# TriggerBoardv2.net
KiCad netlist of a schematic drawn in EAGLE
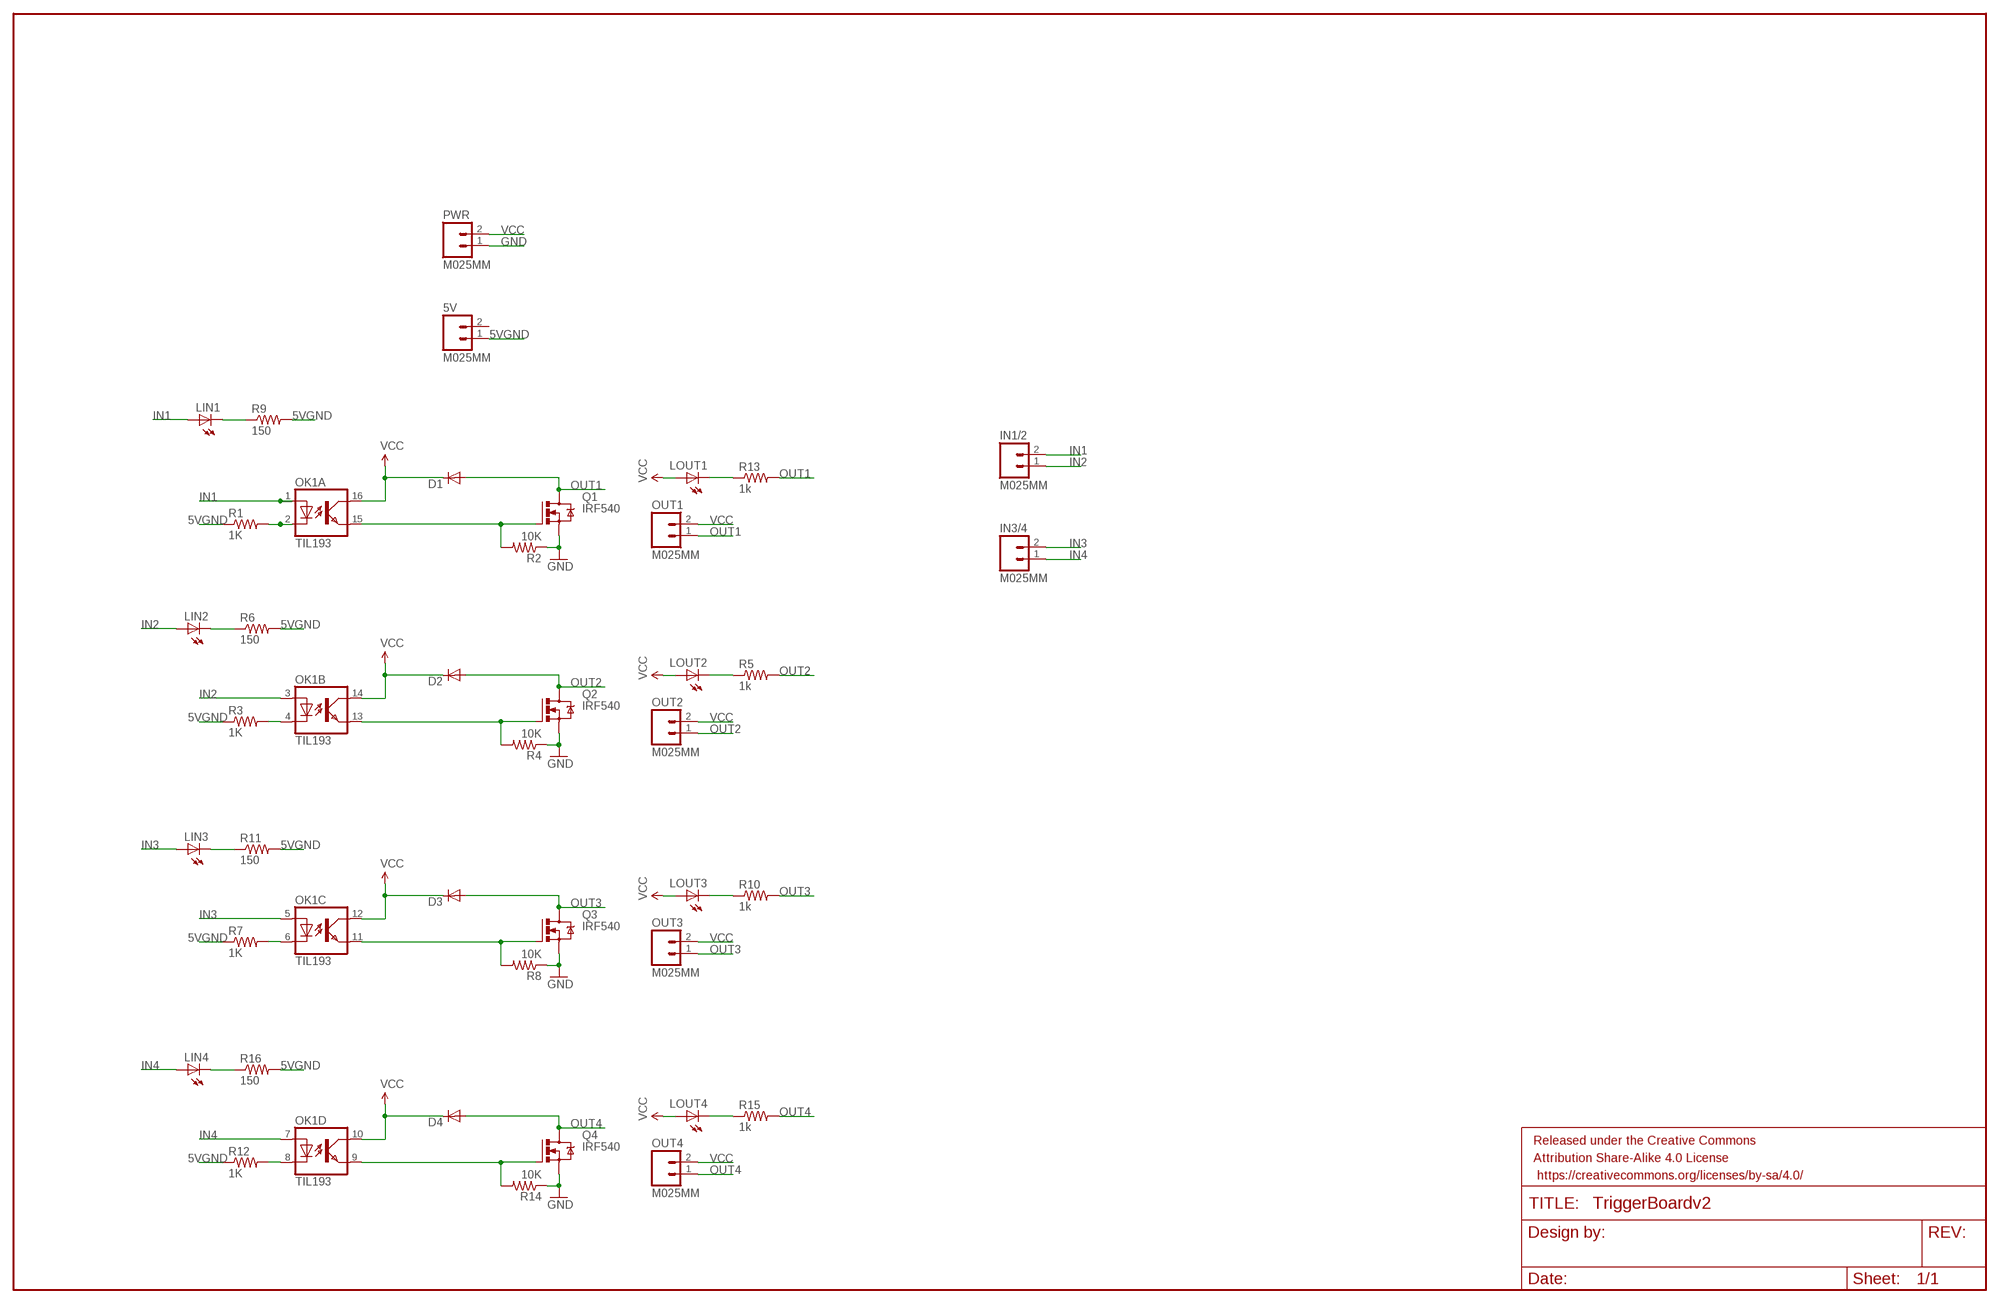
[diagram p0: schematic, sheet 1]

(export (version "E")
  (design (tool "Eeschema 10.0.6"))
  (components
    (comp (ref "5V")
      (value "M025MM")
      (footprint "eagle-import:SCREWTERMINAL-5MM-2")
      (libsource (lib "eagle-import") (part "M025MM"))
    )
    (comp (ref "D1")
      (value "DIODEPTH")
      (footprint "eagle-import:DIODE-1N4001")
      (libsource (lib "eagle-import") (part "DIODEPTH"))
    )
    (comp (ref "D2")
      (value "DIODEPTH")
      (footprint "eagle-import:DIODE-1N4001")
      (libsource (lib "eagle-import") (part "DIODEPTH"))
    )
    (comp (ref "D3")
      (value "DIODEPTH")
      (footprint "eagle-import:DIODE-1N4001")
      (libsource (lib "eagle-import") (part "DIODEPTH"))
    )
    (comp (ref "D4")
      (value "DIODEPTH")
      (footprint "eagle-import:DIODE-1N4001")
      (libsource (lib "eagle-import") (part "DIODEPTH"))
    )
    (comp (ref "FRAME1")
      (value "FRAME-LEDGER")
      (footprint "eagle-import:CREATIVE_COMMONS")
      (libsource (lib "eagle-import") (part "FRAME-LEDGER"))
    )
    (comp (ref "IN1/2")
      (value "M025MM")
      (footprint "eagle-import:SCREWTERMINAL-5MM-2")
      (libsource (lib "eagle-import") (part "M025MM"))
    )
    (comp (ref "IN3/4")
      (value "M025MM")
      (footprint "eagle-import:SCREWTERMINAL-5MM-2")
      (libsource (lib "eagle-import") (part "M025MM"))
    )
    (comp (ref "LIN1")
      (value "LED3MM")
      (footprint "eagle-import:LED3MM")
      (libsource (lib "eagle-import") (part "LED3MM"))
    )
    (comp (ref "LIN2")
      (value "LED3MM")
      (footprint "eagle-import:LED3MM")
      (libsource (lib "eagle-import") (part "LED3MM"))
    )
    (comp (ref "LIN3")
      (value "LED3MM")
      (footprint "eagle-import:LED3MM")
      (libsource (lib "eagle-import") (part "LED3MM"))
    )
    (comp (ref "LIN4")
      (value "LED3MM")
      (footprint "eagle-import:LED3MM")
      (libsource (lib "eagle-import") (part "LED3MM"))
    )
    (comp (ref "LOUT1")
      (value "LED3MM")
      (footprint "eagle-import:LED3MM")
      (libsource (lib "eagle-import") (part "LED3MM"))
    )
    (comp (ref "LOUT2")
      (value "LED3MM")
      (footprint "eagle-import:LED3MM")
      (libsource (lib "eagle-import") (part "LED3MM"))
    )
    (comp (ref "LOUT3")
      (value "LED3MM")
      (footprint "eagle-import:LED3MM")
      (libsource (lib "eagle-import") (part "LED3MM"))
    )
    (comp (ref "LOUT4")
      (value "LED3MM")
      (footprint "eagle-import:LED3MM")
      (libsource (lib "eagle-import") (part "LED3MM"))
    )
    (comp (ref "OK1")
      (value "TIL193")
      (footprint "eagle-import:DIL16")
      (libsource (lib "eagle-import") (part "TIL193"))
    )
    (comp (ref "OUT1")
      (value "M025MM")
      (footprint "eagle-import:SCREWTERMINAL-5MM-2")
      (libsource (lib "eagle-import") (part "M025MM"))
    )
    (comp (ref "OUT2")
      (value "M025MM")
      (footprint "eagle-import:SCREWTERMINAL-5MM-2")
      (libsource (lib "eagle-import") (part "M025MM"))
    )
    (comp (ref "OUT3")
      (value "M025MM")
      (footprint "eagle-import:SCREWTERMINAL-5MM-2")
      (libsource (lib "eagle-import") (part "M025MM"))
    )
    (comp (ref "OUT4")
      (value "M025MM")
      (footprint "eagle-import:SCREWTERMINAL-5MM-2")
      (libsource (lib "eagle-import") (part "M025MM"))
    )
    (comp (ref "PWR")
      (value "M025MM")
      (footprint "eagle-import:SCREWTERMINAL-5MM-2")
      (libsource (lib "eagle-import") (part "M025MM"))
    )
    (comp (ref "Q1")
      (value "IRF540")
      (footprint "eagle-import:TO220BV")
      (libsource (lib "eagle-import") (part "IRF540"))
    )
    (comp (ref "Q2")
      (value "IRF540")
      (footprint "eagle-import:TO220BV")
      (libsource (lib "eagle-import") (part "IRF540"))
    )
    (comp (ref "Q3")
      (value "IRF540")
      (footprint "eagle-import:TO220BV")
      (libsource (lib "eagle-import") (part "IRF540"))
    )
    (comp (ref "Q4")
      (value "IRF540")
      (footprint "eagle-import:TO220BV")
      (libsource (lib "eagle-import") (part "IRF540"))
    )
    (comp (ref "R1")
      (value "1K")
      (footprint "eagle-import:AXIAL-0.4")
      (libsource (lib "eagle-import") (part "RESISTORPTH-1/4W"))
    )
    (comp (ref "R2")
      (value "10K")
      (footprint "eagle-import:AXIAL-0.4")
      (libsource (lib "eagle-import") (part "RESISTORPTH-1/4W"))
    )
    (comp (ref "R3")
      (value "1K")
      (footprint "eagle-import:AXIAL-0.4")
      (libsource (lib "eagle-import") (part "RESISTORPTH-1/4W"))
    )
    (comp (ref "R4")
      (value "10K")
      (footprint "eagle-import:AXIAL-0.4")
      (libsource (lib "eagle-import") (part "RESISTORPTH-1/4W"))
    )
    (comp (ref "R5")
      (value "1k")
      (footprint "eagle-import:AXIAL-0.4")
      (libsource (lib "eagle-import") (part "RESISTORPTH-1/4W"))
    )
    (comp (ref "R6")
      (value "150")
      (footprint "eagle-import:AXIAL-0.4")
      (libsource (lib "eagle-import") (part "RESISTORPTH-1/4W"))
    )
    (comp (ref "R7")
      (value "1K")
      (footprint "eagle-import:AXIAL-0.4")
      (libsource (lib "eagle-import") (part "RESISTORPTH-1/4W"))
    )
    (comp (ref "R8")
      (value "10K")
      (footprint "eagle-import:AXIAL-0.4")
      (libsource (lib "eagle-import") (part "RESISTORPTH-1/4W"))
    )
    (comp (ref "R9")
      (value "150")
      (footprint "eagle-import:AXIAL-0.4")
      (libsource (lib "eagle-import") (part "RESISTORPTH-1/4W"))
    )
    (comp (ref "R10")
      (value "1k")
      (footprint "eagle-import:AXIAL-0.4")
      (libsource (lib "eagle-import") (part "RESISTORPTH-1/4W"))
    )
    (comp (ref "R11")
      (value "150")
      (footprint "eagle-import:AXIAL-0.4")
      (libsource (lib "eagle-import") (part "RESISTORPTH-1/4W"))
    )
    (comp (ref "R12")
      (value "1K")
      (footprint "eagle-import:AXIAL-0.4")
      (libsource (lib "eagle-import") (part "RESISTORPTH-1/4W"))
    )
    (comp (ref "R13")
      (value "1k")
      (footprint "eagle-import:AXIAL-0.4")
      (libsource (lib "eagle-import") (part "RESISTORPTH-1/4W"))
    )
    (comp (ref "R14")
      (value "10K")
      (footprint "eagle-import:AXIAL-0.4")
      (libsource (lib "eagle-import") (part "RESISTORPTH-1/4W"))
    )
    (comp (ref "R15")
      (value "1k")
      (footprint "eagle-import:AXIAL-0.4")
      (libsource (lib "eagle-import") (part "RESISTORPTH-1/4W"))
    )
    (comp (ref "R16")
      (value "150")
      (footprint "eagle-import:AXIAL-0.4")
      (libsource (lib "eagle-import") (part "RESISTORPTH-1/4W"))
    )
  )
  (nets
    (net (code "1") (name "/5VGND") (class "Default")
      (node (ref "5V") (pin "1") (pinfunction "1_1") (pintype "passive"))
      (node (ref "R1") (pin "P$1") (pinfunction "1_P$1") (pintype "passive"))
      (node (ref "R11") (pin "P$2") (pinfunction "2_P$2") (pintype "passive"))
      (node (ref "R12") (pin "P$1") (pinfunction "1_P$1") (pintype "passive"))
      (node (ref "R16") (pin "P$2") (pinfunction "2_P$2") (pintype "passive"))
      (node (ref "R3") (pin "P$1") (pinfunction "1_P$1") (pintype "passive"))
      (node (ref "R6") (pin "P$2") (pinfunction "2_P$2") (pintype "passive"))
      (node (ref "R7") (pin "P$1") (pinfunction "1_P$1") (pintype "passive"))
      (node (ref "R9") (pin "P$2") (pinfunction "2_P$2") (pintype "passive"))
    )
    (net (code "2") (name "/IN1") (class "Default")
      (node (ref "IN1/2") (pin "2") (pinfunction "2_2") (pintype "passive"))
      (node (ref "LIN1") (pin "A") (pinfunction "A_A") (pintype "passive"))
      (node (ref "OK1") (pin "1") (pinfunction "A_1") (pintype "passive"))
    )
    (net (code "3") (name "/IN2") (class "Default")
      (node (ref "IN1/2") (pin "1") (pinfunction "1_1") (pintype "passive"))
      (node (ref "LIN2") (pin "A") (pinfunction "A_A") (pintype "passive"))
      (node (ref "OK1") (pin "3") (pinfunction "A_3") (pintype "passive"))
    )
    (net (code "4") (name "/IN3") (class "Default")
      (node (ref "IN3/4") (pin "2") (pinfunction "2_2") (pintype "passive"))
      (node (ref "LIN3") (pin "A") (pinfunction "A_A") (pintype "passive"))
      (node (ref "OK1") (pin "5") (pinfunction "A_5") (pintype "passive"))
    )
    (net (code "5") (name "/IN4") (class "Default")
      (node (ref "IN3/4") (pin "1") (pinfunction "1_1") (pintype "passive"))
      (node (ref "LIN4") (pin "A") (pinfunction "A_A") (pintype "passive"))
      (node (ref "OK1") (pin "7") (pinfunction "A_7") (pintype "passive"))
    )
    (net (code "6") (name "/OUT1") (class "Default")
      (node (ref "D1") (pin "A") (pinfunction "A_A") (pintype "passive"))
      (node (ref "OUT1") (pin "1") (pinfunction "1_1") (pintype "passive"))
      (node (ref "Q1") (pin "D") (pinfunction "D_D") (pintype "passive"))
      (node (ref "R13") (pin "P$2") (pinfunction "2_P$2") (pintype "passive"))
    )
    (net (code "7") (name "/OUT2") (class "Default")
      (node (ref "D2") (pin "A") (pinfunction "A_A") (pintype "passive"))
      (node (ref "OUT2") (pin "1") (pinfunction "1_1") (pintype "passive"))
      (node (ref "Q2") (pin "D") (pinfunction "D_D") (pintype "passive"))
      (node (ref "R5") (pin "P$2") (pinfunction "2_P$2") (pintype "passive"))
    )
    (net (code "8") (name "/OUT3") (class "Default")
      (node (ref "D3") (pin "A") (pinfunction "A_A") (pintype "passive"))
      (node (ref "OUT3") (pin "1") (pinfunction "1_1") (pintype "passive"))
      (node (ref "Q3") (pin "D") (pinfunction "D_D") (pintype "passive"))
      (node (ref "R10") (pin "P$2") (pinfunction "2_P$2") (pintype "passive"))
    )
    (net (code "9") (name "/OUT4") (class "Default")
      (node (ref "D4") (pin "A") (pinfunction "A_A") (pintype "passive"))
      (node (ref "OUT4") (pin "1") (pinfunction "1_1") (pintype "passive"))
      (node (ref "Q4") (pin "D") (pinfunction "D_D") (pintype "passive"))
      (node (ref "R15") (pin "P$2") (pinfunction "2_P$2") (pintype "passive"))
    )
    (net (code "10") (name "GND") (class "Default")
      (node (ref "PWR") (pin "1") (pinfunction "1_1") (pintype "passive"))
      (node (ref "Q1") (pin "S") (pinfunction "S_S") (pintype "passive"))
      (node (ref "Q2") (pin "S") (pinfunction "S_S") (pintype "passive"))
      (node (ref "Q3") (pin "S") (pinfunction "S_S") (pintype "passive"))
      (node (ref "Q4") (pin "S") (pinfunction "S_S") (pintype "passive"))
      (node (ref "R14") (pin "P$1") (pinfunction "1_P$1") (pintype "passive"))
      (node (ref "R2") (pin "P$1") (pinfunction "1_P$1") (pintype "passive"))
      (node (ref "R4") (pin "P$1") (pinfunction "1_P$1") (pintype "passive"))
      (node (ref "R8") (pin "P$1") (pinfunction "1_P$1") (pintype "passive"))
    )
    (net (code "11") (name "Net-(LIN1-C)") (class "Default")
      (node (ref "LIN1") (pin "K") (pinfunction "C_K") (pintype "passive"))
      (node (ref "R9") (pin "P$1") (pinfunction "1_P$1") (pintype "passive"))
    )
    (net (code "12") (name "Net-(LIN2-C)") (class "Default")
      (node (ref "LIN2") (pin "K") (pinfunction "C_K") (pintype "passive"))
      (node (ref "R6") (pin "P$1") (pinfunction "1_P$1") (pintype "passive"))
    )
    (net (code "13") (name "Net-(LIN3-C)") (class "Default")
      (node (ref "LIN3") (pin "K") (pinfunction "C_K") (pintype "passive"))
      (node (ref "R11") (pin "P$1") (pinfunction "1_P$1") (pintype "passive"))
    )
    (net (code "14") (name "Net-(LIN4-C)") (class "Default")
      (node (ref "LIN4") (pin "K") (pinfunction "C_K") (pintype "passive"))
      (node (ref "R16") (pin "P$1") (pinfunction "1_P$1") (pintype "passive"))
    )
    (net (code "15") (name "Net-(LOUT1-C)") (class "Default")
      (node (ref "LOUT1") (pin "K") (pinfunction "C_K") (pintype "passive"))
      (node (ref "R13") (pin "P$1") (pinfunction "1_P$1") (pintype "passive"))
    )
    (net (code "16") (name "Net-(LOUT2-C)") (class "Default")
      (node (ref "LOUT2") (pin "K") (pinfunction "C_K") (pintype "passive"))
      (node (ref "R5") (pin "P$1") (pinfunction "1_P$1") (pintype "passive"))
    )
    (net (code "17") (name "Net-(LOUT3-C)") (class "Default")
      (node (ref "LOUT3") (pin "K") (pinfunction "C_K") (pintype "passive"))
      (node (ref "R10") (pin "P$1") (pinfunction "1_P$1") (pintype "passive"))
    )
    (net (code "18") (name "Net-(LOUT4-C)") (class "Default")
      (node (ref "LOUT4") (pin "K") (pinfunction "C_K") (pintype "passive"))
      (node (ref "R15") (pin "P$1") (pinfunction "1_P$1") (pintype "passive"))
    )
    (net (code "19") (name "Net-(OK1A-C)") (class "Default")
      (node (ref "OK1") (pin "2") (pinfunction "C_2") (pintype "passive"))
      (node (ref "R1") (pin "P$2") (pinfunction "2_P$2") (pintype "passive"))
    )
    (net (code "20") (name "Net-(OK1A-EMIT)") (class "Default")
      (node (ref "OK1") (pin "15") (pinfunction "EMIT_15") (pintype "passive"))
      (node (ref "Q1") (pin "G") (pinfunction "G_G") (pintype "passive"))
      (node (ref "R2") (pin "P$2") (pinfunction "2_P$2") (pintype "passive"))
    )
    (net (code "21") (name "Net-(OK1B-C)") (class "Default")
      (node (ref "OK1") (pin "4") (pinfunction "C_4") (pintype "passive"))
      (node (ref "R3") (pin "P$2") (pinfunction "2_P$2") (pintype "passive"))
    )
    (net (code "22") (name "Net-(OK1B-EMIT)") (class "Default")
      (node (ref "OK1") (pin "13") (pinfunction "EMIT_13") (pintype "passive"))
      (node (ref "Q2") (pin "G") (pinfunction "G_G") (pintype "passive"))
      (node (ref "R4") (pin "P$2") (pinfunction "2_P$2") (pintype "passive"))
    )
    (net (code "23") (name "Net-(OK1C-C)") (class "Default")
      (node (ref "OK1") (pin "6") (pinfunction "C_6") (pintype "passive"))
      (node (ref "R7") (pin "P$2") (pinfunction "2_P$2") (pintype "passive"))
    )
    (net (code "24") (name "Net-(OK1C-EMIT)") (class "Default")
      (node (ref "OK1") (pin "11") (pinfunction "EMIT_11") (pintype "passive"))
      (node (ref "Q3") (pin "G") (pinfunction "G_G") (pintype "passive"))
      (node (ref "R8") (pin "P$2") (pinfunction "2_P$2") (pintype "passive"))
    )
    (net (code "25") (name "Net-(OK1D-C)") (class "Default")
      (node (ref "OK1") (pin "8") (pinfunction "C_8") (pintype "passive"))
      (node (ref "R12") (pin "P$2") (pinfunction "2_P$2") (pintype "passive"))
    )
    (net (code "26") (name "Net-(OK1D-EMIT)") (class "Default")
      (node (ref "OK1") (pin "9") (pinfunction "EMIT_9") (pintype "passive"))
      (node (ref "Q4") (pin "G") (pinfunction "G_G") (pintype "passive"))
      (node (ref "R14") (pin "P$2") (pinfunction "2_P$2") (pintype "passive"))
    )
    (net (code "27") (name "VCC") (class "Default")
      (node (ref "D1") (pin "C") (pinfunction "C_C") (pintype "passive"))
      (node (ref "D2") (pin "C") (pinfunction "C_C") (pintype "passive"))
      (node (ref "D3") (pin "C") (pinfunction "C_C") (pintype "passive"))
      (node (ref "D4") (pin "C") (pinfunction "C_C") (pintype "passive"))
      (node (ref "LOUT1") (pin "A") (pinfunction "A_A") (pintype "passive"))
      (node (ref "LOUT2") (pin "A") (pinfunction "A_A") (pintype "passive"))
      (node (ref "LOUT3") (pin "A") (pinfunction "A_A") (pintype "passive"))
      (node (ref "LOUT4") (pin "A") (pinfunction "A_A") (pintype "passive"))
      (node (ref "OK1") (pin "10") (pinfunction "COL_10") (pintype "passive"))
      (node (ref "OK1") (pin "12") (pinfunction "COL_12") (pintype "passive"))
      (node (ref "OK1") (pin "14") (pinfunction "COL_14") (pintype "passive"))
      (node (ref "OK1") (pin "16") (pinfunction "COL_16") (pintype "passive"))
      (node (ref "OUT1") (pin "2") (pinfunction "2_2") (pintype "passive"))
      (node (ref "OUT2") (pin "2") (pinfunction "2_2") (pintype "passive"))
      (node (ref "OUT3") (pin "2") (pinfunction "2_2") (pintype "passive"))
      (node (ref "OUT4") (pin "2") (pinfunction "2_2") (pintype "passive"))
      (node (ref "PWR") (pin "2") (pinfunction "2_2") (pintype "passive"))
    )
    (net (code "28") (name "unconnected-(5V-Pad2)") (class "Default")
      (node (ref "5V") (pin "2") (pinfunction "2_2") (pintype "passive"))
    )
  )
)
